# Link232-wifi.net
KiCad netlist of a schematic drawn in EAGLE
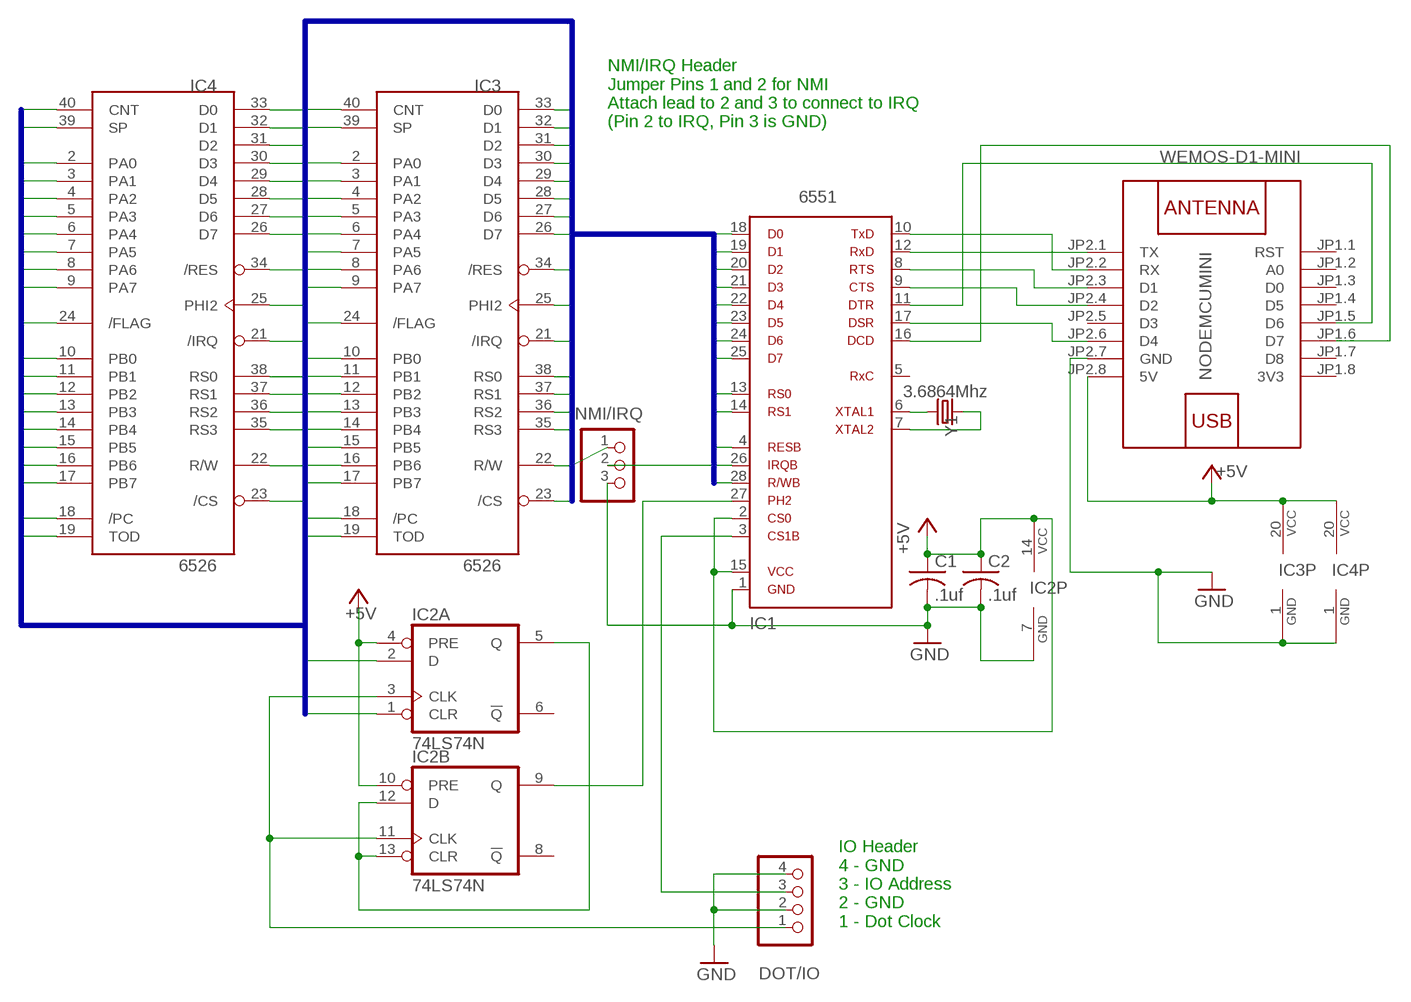
[diagram p0: schematic, sheet 1]

(export (version "E")
  (design (tool "Eeschema 10.0.6"))
  (components
    (comp (ref "C1")
      (value ".1uf")
      (footprint "eagle-import:C050-024X044")
      (libsource (lib "eagle-import") (part "C-US050-024X044"))
    )
    (comp (ref "C2")
      (value ".1uf")
      (footprint "eagle-import:C050-024X044")
      (libsource (lib "eagle-import") (part "C-US050-024X044"))
    )
    (comp (ref "DOT/IO")
      (value "PINHD-1X4")
      (footprint "eagle-import:1X04")
      (libsource (lib "eagle-import") (part "PINHD-1X4"))
    )
    (comp (ref "IC1")
      (value "6551")
      (footprint "eagle-import:6551")
      (libsource (lib "eagle-import") (part "6551"))
    )
    (comp (ref "IC2")
      (value "74LS74N")
      (footprint "eagle-import:DIL14")
      (libsource (lib "eagle-import") (part "7474NLS"))
    )
    (comp (ref "IC3")
      (value "6526")
      (footprint "eagle-import:DIP40")
      (libsource (lib "eagle-import") (part "6526"))
    )
    (comp (ref "IC4")
      (value "6526")
      (footprint "eagle-import:DIP40")
      (libsource (lib "eagle-import") (part "6526"))
    )
    (comp (ref "JP1")
      (value "NMI/IRQ")
      (footprint "eagle-import:1X03")
      (libsource (lib "eagle-import") (part "PINHD-1X3"))
    )
    (comp (ref "NODEMCUMINI")
      (value "WEMOS-D1-MINI")
      (footprint "eagle-import:WEMOS-D1-MINI")
      (libsource (lib "eagle-import") (part "WEMOS-D1-MINI"))
    )
    (comp (ref "Y1")
      (value "3.6864Mhz")
      (footprint "eagle-import:HC49US")
      (libsource (lib "eagle-import") (part "CRYSTALPTH-HC49US"))
    )
  )
  (nets
    (net (code "1") (name "+5V") (class "Default")
      (node (ref "C1") (pin "1") (pinfunction "1_1") (pintype "passive"))
      (node (ref "C2") (pin "1") (pinfunction "1_1") (pintype "passive"))
      (node (ref "IC1") (pin "15") (pinfunction "15_15") (pintype "passive"))
      (node (ref "IC1") (pin "2") (pinfunction "2_2") (pintype "passive"))
      (node (ref "IC2") (pin "10") (pinfunction "PRE_10") (pintype "input"))
      (node (ref "IC2") (pin "14") (pinfunction "VCC_14") (pintype "power_in"))
      (node (ref "IC2") (pin "4") (pinfunction "PRE_4") (pintype "input"))
      (node (ref "IC3") (pin "20") (pinfunction "VCC_20") (pintype "power_in"))
      (node (ref "IC4") (pin "20") (pinfunction "VCC_20") (pintype "power_in"))
      (node (ref "NODEMCUMINI") (pin "JP2.8") (pinfunction "5V_JP2.8") (pintype "power_in"))
    )
    (net (code "2") (name "/3V3") (class "Default")
      (node (ref "NODEMCUMINI") (pin "JP1.8") (pinfunction "3V3_JP1.8") (pintype "power_in"))
    )
    (net (code "3") (name "/CNT") (class "Default")
      (node (ref "IC3") (pin "40") (pinfunction "CNT_40") (pintype "input"))
      (node (ref "IC4") (pin "40") (pinfunction "CNT_40") (pintype "input"))
    )
    (net (code "4") (name "/D0") (class "Default")
      (node (ref "IC1") (pin "18") (pinfunction "18_18") (pintype "passive"))
      (node (ref "IC3") (pin "33") (pinfunction "D0_33") (pintype "bidirectional"))
      (node (ref "IC4") (pin "33") (pinfunction "D0_33") (pintype "bidirectional"))
    )
    (net (code "5") (name "/D1") (class "Default")
      (node (ref "IC1") (pin "19") (pinfunction "19_19") (pintype "passive"))
      (node (ref "IC3") (pin "32") (pinfunction "D1_32") (pintype "bidirectional"))
      (node (ref "IC4") (pin "32") (pinfunction "D1_32") (pintype "bidirectional"))
    )
    (net (code "6") (name "/D2") (class "Default")
      (node (ref "IC1") (pin "20") (pinfunction "20_20") (pintype "passive"))
      (node (ref "IC3") (pin "31") (pinfunction "D2_31") (pintype "bidirectional"))
      (node (ref "IC4") (pin "31") (pinfunction "D2_31") (pintype "bidirectional"))
    )
    (net (code "7") (name "/D3") (class "Default")
      (node (ref "IC1") (pin "21") (pinfunction "21_21") (pintype "passive"))
      (node (ref "IC3") (pin "30") (pinfunction "D3_30") (pintype "bidirectional"))
      (node (ref "IC4") (pin "30") (pinfunction "D3_30") (pintype "bidirectional"))
    )
    (net (code "8") (name "/D4") (class "Default")
      (node (ref "IC1") (pin "22") (pinfunction "22_22") (pintype "passive"))
      (node (ref "IC3") (pin "29") (pinfunction "D4_29") (pintype "bidirectional"))
      (node (ref "IC4") (pin "29") (pinfunction "D4_29") (pintype "bidirectional"))
    )
    (net (code "9") (name "/D5") (class "Default")
      (node (ref "IC1") (pin "23") (pinfunction "23_23") (pintype "passive"))
      (node (ref "IC3") (pin "28") (pinfunction "D5_28") (pintype "bidirectional"))
      (node (ref "IC4") (pin "28") (pinfunction "D5_28") (pintype "bidirectional"))
    )
    (net (code "10") (name "/D6") (class "Default")
      (node (ref "IC1") (pin "24") (pinfunction "24_24") (pintype "passive"))
      (node (ref "IC3") (pin "27") (pinfunction "D6_27") (pintype "bidirectional"))
      (node (ref "IC4") (pin "27") (pinfunction "D6_27") (pintype "bidirectional"))
    )
    (net (code "11") (name "/D7") (class "Default")
      (node (ref "IC1") (pin "25") (pinfunction "25_25") (pintype "passive"))
      (node (ref "IC3") (pin "26") (pinfunction "D7_26") (pintype "bidirectional"))
      (node (ref "IC4") (pin "26") (pinfunction "D7_26") (pintype "bidirectional"))
    )
    (net (code "12") (name "/IRQ") (class "Default")
      (node (ref "IC3") (pin "21") (pinfunction "/IRQ_21") (pintype "open_collector"))
      (node (ref "IC4") (pin "21") (pinfunction "/IRQ_21") (pintype "open_collector"))
      (node (ref "JP1") (pin "1") (pinfunction "1_1") (pintype "passive"))
    )
    (net (code "13") (name "/PA0") (class "Default")
      (node (ref "IC3") (pin "2") (pinfunction "PA0_2") (pintype "bidirectional"))
      (node (ref "IC4") (pin "2") (pinfunction "PA0_2") (pintype "bidirectional"))
    )
    (net (code "14") (name "/PA1") (class "Default")
      (node (ref "IC3") (pin "3") (pinfunction "PA1_3") (pintype "bidirectional"))
      (node (ref "IC4") (pin "3") (pinfunction "PA1_3") (pintype "bidirectional"))
    )
    (net (code "15") (name "/PA2") (class "Default")
      (node (ref "IC3") (pin "4") (pinfunction "PA2_4") (pintype "bidirectional"))
      (node (ref "IC4") (pin "4") (pinfunction "PA2_4") (pintype "bidirectional"))
    )
    (net (code "16") (name "/PA3") (class "Default")
      (node (ref "IC3") (pin "5") (pinfunction "PA3_5") (pintype "bidirectional"))
      (node (ref "IC4") (pin "5") (pinfunction "PA3_5") (pintype "bidirectional"))
    )
    (net (code "17") (name "/PA4") (class "Default")
      (node (ref "IC3") (pin "6") (pinfunction "PA4_6") (pintype "bidirectional"))
      (node (ref "IC4") (pin "6") (pinfunction "PA4_6") (pintype "bidirectional"))
    )
    (net (code "18") (name "/PA5") (class "Default")
      (node (ref "IC3") (pin "7") (pinfunction "PA5_7") (pintype "bidirectional"))
      (node (ref "IC4") (pin "7") (pinfunction "PA5_7") (pintype "bidirectional"))
    )
    (net (code "19") (name "/PA6") (class "Default")
      (node (ref "IC3") (pin "8") (pinfunction "PA6_8") (pintype "bidirectional"))
      (node (ref "IC4") (pin "8") (pinfunction "PA6_8") (pintype "bidirectional"))
    )
    (net (code "20") (name "/PA7") (class "Default")
      (node (ref "IC3") (pin "9") (pinfunction "PA7_9") (pintype "bidirectional"))
      (node (ref "IC4") (pin "9") (pinfunction "PA7_9") (pintype "bidirectional"))
    )
    (net (code "21") (name "/PB0") (class "Default")
      (node (ref "IC3") (pin "10") (pinfunction "PB0_10") (pintype "bidirectional"))
      (node (ref "IC4") (pin "10") (pinfunction "PB0_10") (pintype "bidirectional"))
    )
    (net (code "22") (name "/PB1") (class "Default")
      (node (ref "IC3") (pin "11") (pinfunction "PB1_11") (pintype "bidirectional"))
      (node (ref "IC4") (pin "11") (pinfunction "PB1_11") (pintype "bidirectional"))
    )
    (net (code "23") (name "/PB2") (class "Default")
      (node (ref "IC3") (pin "12") (pinfunction "PB2_12") (pintype "bidirectional"))
      (node (ref "IC4") (pin "12") (pinfunction "PB2_12") (pintype "bidirectional"))
    )
    (net (code "24") (name "/PB3") (class "Default")
      (node (ref "IC3") (pin "13") (pinfunction "PB3_13") (pintype "bidirectional"))
      (node (ref "IC4") (pin "13") (pinfunction "PB3_13") (pintype "bidirectional"))
    )
    (net (code "25") (name "/PB4") (class "Default")
      (node (ref "IC3") (pin "14") (pinfunction "PB4_14") (pintype "bidirectional"))
      (node (ref "IC4") (pin "14") (pinfunction "PB4_14") (pintype "bidirectional"))
    )
    (net (code "26") (name "/PB5") (class "Default")
      (node (ref "IC3") (pin "15") (pinfunction "PB5_15") (pintype "bidirectional"))
      (node (ref "IC4") (pin "15") (pinfunction "PB5_15") (pintype "bidirectional"))
    )
    (net (code "27") (name "/PB6") (class "Default")
      (node (ref "IC3") (pin "16") (pinfunction "PB6_16") (pintype "bidirectional"))
      (node (ref "IC4") (pin "16") (pinfunction "PB6_16") (pintype "bidirectional"))
    )
    (net (code "28") (name "/PB7") (class "Default")
      (node (ref "IC3") (pin "17") (pinfunction "PB7_17") (pintype "bidirectional"))
      (node (ref "IC4") (pin "17") (pinfunction "PB7_17") (pintype "bidirectional"))
    )
    (net (code "29") (name "/PHI2") (class "Default")
      (node (ref "IC2") (pin "1") (pinfunction "CLR_1") (pintype "input"))
      (node (ref "IC2") (pin "2") (pinfunction "D_2") (pintype "input"))
      (node (ref "IC3") (pin "25") (pinfunction "PHI2_25") (pintype "input"))
      (node (ref "IC4") (pin "25") (pinfunction "PHI2_25") (pintype "input"))
    )
    (net (code "30") (name "/RES") (class "Default")
      (node (ref "IC1") (pin "4") (pinfunction "4_4") (pintype "passive"))
      (node (ref "IC3") (pin "34") (pinfunction "/RES_34") (pintype "input"))
      (node (ref "IC4") (pin "34") (pinfunction "/RES_34") (pintype "input"))
    )
    (net (code "31") (name "/RS0") (class "Default")
      (node (ref "IC1") (pin "13") (pinfunction "13_13") (pintype "passive"))
      (node (ref "IC3") (pin "38") (pinfunction "RS0_38") (pintype "input"))
      (node (ref "IC4") (pin "38") (pinfunction "RS0_38") (pintype "input"))
    )
    (net (code "32") (name "/RS1") (class "Default")
      (node (ref "IC1") (pin "14") (pinfunction "14_14") (pintype "passive"))
      (node (ref "IC3") (pin "37") (pinfunction "RS1_37") (pintype "input"))
      (node (ref "IC4") (pin "37") (pinfunction "RS1_37") (pintype "input"))
    )
    (net (code "33") (name "/RS2") (class "Default")
      (node (ref "IC3") (pin "36") (pinfunction "RS2_36") (pintype "input"))
      (node (ref "IC4") (pin "36") (pinfunction "RS2_36") (pintype "input"))
    )
    (net (code "34") (name "/RS3") (class "Default")
      (node (ref "IC3") (pin "35") (pinfunction "RS3_35") (pintype "input"))
      (node (ref "IC4") (pin "35") (pinfunction "RS3_35") (pintype "input"))
    )
    (net (code "35") (name "/RW") (class "Default")
      (node (ref "IC1") (pin "28") (pinfunction "28_28") (pintype "passive"))
      (node (ref "IC3") (pin "22") (pinfunction "R/W_22") (pintype "input"))
      (node (ref "IC4") (pin "22") (pinfunction "R/W_22") (pintype "input"))
    )
    (net (code "36") (name "/SP") (class "Default")
      (node (ref "IC3") (pin "39") (pinfunction "SP_39") (pintype "bidirectional"))
      (node (ref "IC4") (pin "39") (pinfunction "SP_39") (pintype "bidirectional"))
    )
    (net (code "37") (name "/TOD") (class "Default")
      (node (ref "IC3") (pin "19") (pinfunction "TOD_19") (pintype "bidirectional"))
      (node (ref "IC4") (pin "19") (pinfunction "TOD_19") (pintype "bidirectional"))
    )
    (net (code "38") (name "/{slash}CS") (class "Default")
      (node (ref "IC3") (pin "23") (pinfunction "/CS_23") (pintype "input"))
      (node (ref "IC4") (pin "23") (pinfunction "/CS_23") (pintype "input"))
    )
    (net (code "39") (name "/{slash}FLAG") (class "Default")
      (node (ref "IC3") (pin "24") (pinfunction "/FLAG_24") (pintype "input"))
      (node (ref "IC4") (pin "24") (pinfunction "/FLAG_24") (pintype "input"))
    )
    (net (code "40") (name "/{slash}PC") (class "Default")
      (node (ref "IC3") (pin "18") (pinfunction "/PC_18") (pintype "bidirectional"))
      (node (ref "IC4") (pin "18") (pinfunction "/PC_18") (pintype "bidirectional"))
    )
    (net (code "41") (name "GND") (class "Default")
      (node (ref "C1") (pin "2") (pinfunction "2_2") (pintype "passive"))
      (node (ref "C2") (pin "2") (pinfunction "2_2") (pintype "passive"))
      (node (ref "DOT/IO") (pin "2") (pinfunction "2_2") (pintype "passive"))
      (node (ref "DOT/IO") (pin "4") (pinfunction "4_4") (pintype "passive"))
      (node (ref "IC1") (pin "1") (pinfunction "1_1") (pintype "passive"))
      (node (ref "IC2") (pin "7") (pinfunction "GND_7") (pintype "power_in"))
      (node (ref "IC3") (pin "1") (pinfunction "GND_1") (pintype "power_in"))
      (node (ref "IC4") (pin "1") (pinfunction "GND_1") (pintype "power_in"))
      (node (ref "JP1") (pin "3") (pinfunction "3_3") (pintype "passive"))
      (node (ref "NODEMCUMINI") (pin "JP2.7") (pinfunction "GND_JP2.7") (pintype "power_in"))
    )
    (net (code "42") (name "Net-(DOT/IO-Pad3)") (class "Default")
      (node (ref "DOT/IO") (pin "3") (pinfunction "3_3") (pintype "passive"))
      (node (ref "IC1") (pin "3") (pinfunction "3_3") (pintype "passive"))
    )
    (net (code "43") (name "Net-(IC1-Pad6)") (class "Default")
      (node (ref "IC1") (pin "6") (pinfunction "6_6") (pintype "passive"))
      (node (ref "Y1") (pin "2") (pinfunction "2_2") (pintype "passive"))
    )
    (net (code "44") (name "Net-(IC1-Pad7)") (class "Default")
      (node (ref "IC1") (pin "7") (pinfunction "7_7") (pintype "passive"))
      (node (ref "Y1") (pin "1") (pinfunction "1_1") (pintype "passive"))
    )
    (net (code "45") (name "Net-(IC1-Pad26)") (class "Default")
      (node (ref "IC1") (pin "26") (pinfunction "26_26") (pintype "passive"))
      (node (ref "JP1") (pin "2") (pinfunction "2_2") (pintype "passive"))
    )
    (net (code "46") (name "Net-(IC2A-CLK)") (class "Default")
      (node (ref "DOT/IO") (pin "1") (pinfunction "1_1") (pintype "passive"))
      (node (ref "IC2") (pin "11") (pinfunction "CLK_11") (pintype "input"))
      (node (ref "IC2") (pin "3") (pinfunction "CLK_3") (pintype "input"))
    )
    (net (code "47") (name "Net-(IC2A-Q)") (class "Default")
      (node (ref "IC2") (pin "12") (pinfunction "D_12") (pintype "input"))
      (node (ref "IC2") (pin "13") (pinfunction "CLR_13") (pintype "input"))
      (node (ref "IC2") (pin "5") (pinfunction "Q_5") (pintype "output"))
    )
    (net (code "48") (name "Net-(IC2B-Q)") (class "Default")
      (node (ref "IC1") (pin "27") (pinfunction "27_27") (pintype "passive"))
      (node (ref "IC2") (pin "9") (pinfunction "Q_9") (pintype "output"))
    )
    (net (code "49") (name "Net-(NODEMCUMINI-D1)") (class "Default")
      (node (ref "IC1") (pin "8") (pinfunction "8_8") (pintype "passive"))
      (node (ref "NODEMCUMINI") (pin "JP2.3") (pinfunction "D1_JP2.3") (pintype "bidirectional"))
    )
    (net (code "50") (name "Net-(NODEMCUMINI-D2)") (class "Default")
      (node (ref "IC1") (pin "9") (pinfunction "9_9") (pintype "passive"))
      (node (ref "NODEMCUMINI") (pin "JP2.4") (pinfunction "D2_JP2.4") (pintype "bidirectional"))
    )
    (net (code "51") (name "Net-(NODEMCUMINI-D4)") (class "Default")
      (node (ref "IC1") (pin "17") (pinfunction "17_17") (pintype "passive"))
      (node (ref "NODEMCUMINI") (pin "JP2.6") (pinfunction "D4_JP2.6") (pintype "bidirectional"))
    )
    (net (code "52") (name "Net-(NODEMCUMINI-D6)") (class "Default")
      (node (ref "IC1") (pin "11") (pinfunction "11_11") (pintype "passive"))
      (node (ref "NODEMCUMINI") (pin "JP1.5") (pinfunction "D6_JP1.5") (pintype "bidirectional"))
    )
    (net (code "53") (name "Net-(NODEMCUMINI-D7)") (class "Default")
      (node (ref "IC1") (pin "16") (pinfunction "16_16") (pintype "passive"))
      (node (ref "NODEMCUMINI") (pin "JP1.6") (pinfunction "D7_JP1.6") (pintype "bidirectional"))
    )
    (net (code "54") (name "Net-(NODEMCUMINI-RX)") (class "Default")
      (node (ref "IC1") (pin "10") (pinfunction "10_10") (pintype "passive"))
      (node (ref "NODEMCUMINI") (pin "JP2.2") (pinfunction "RX_JP2.2") (pintype "bidirectional"))
    )
    (net (code "55") (name "Net-(NODEMCUMINI-TX)") (class "Default")
      (node (ref "IC1") (pin "12") (pinfunction "12_12") (pintype "passive"))
      (node (ref "NODEMCUMINI") (pin "JP2.1") (pinfunction "TX_JP2.1") (pintype "bidirectional"))
    )
    (net (code "56") (name "unconnected-(IC1-Pad5)") (class "Default")
      (node (ref "IC1") (pin "5") (pinfunction "5_5") (pintype "passive"))
    )
    (net (code "57") (name "unconnected-(IC2A-~{Q}-Pad6)") (class "Default")
      (node (ref "IC2") (pin "6") (pinfunction "~{Q}_6") (pintype "output"))
    )
    (net (code "58") (name "unconnected-(IC2B-~{Q}-Pad8)") (class "Default")
      (node (ref "IC2") (pin "8") (pinfunction "~{Q}_8") (pintype "output"))
    )
    (net (code "59") (name "unconnected-(NODEMCUMINI-A0-PadJP1.2)") (class "Default")
      (node (ref "NODEMCUMINI") (pin "JP1.2") (pinfunction "A0_JP1.2") (pintype "bidirectional"))
    )
    (net (code "60") (name "unconnected-(NODEMCUMINI-D0-PadJP1.3)") (class "Default")
      (node (ref "NODEMCUMINI") (pin "JP1.3") (pinfunction "D0_JP1.3") (pintype "bidirectional"))
    )
    (net (code "61") (name "unconnected-(NODEMCUMINI-D3-PadJP2.5)") (class "Default")
      (node (ref "NODEMCUMINI") (pin "JP2.5") (pinfunction "D3_JP2.5") (pintype "bidirectional"))
    )
    (net (code "62") (name "unconnected-(NODEMCUMINI-D5-PadJP1.4)") (class "Default")
      (node (ref "NODEMCUMINI") (pin "JP1.4") (pinfunction "D5_JP1.4") (pintype "bidirectional"))
    )
    (net (code "63") (name "unconnected-(NODEMCUMINI-D8-PadJP1.7)") (class "Default")
      (node (ref "NODEMCUMINI") (pin "JP1.7") (pinfunction "D8_JP1.7") (pintype "bidirectional"))
    )
    (net (code "64") (name "unconnected-(NODEMCUMINI-RST-PadJP1.1)") (class "Default")
      (node (ref "NODEMCUMINI") (pin "JP1.1") (pinfunction "RST_JP1.1") (pintype "bidirectional"))
    )
  )
)
